# pectus.net
KiCad netlist of a schematic drawn in EAGLE
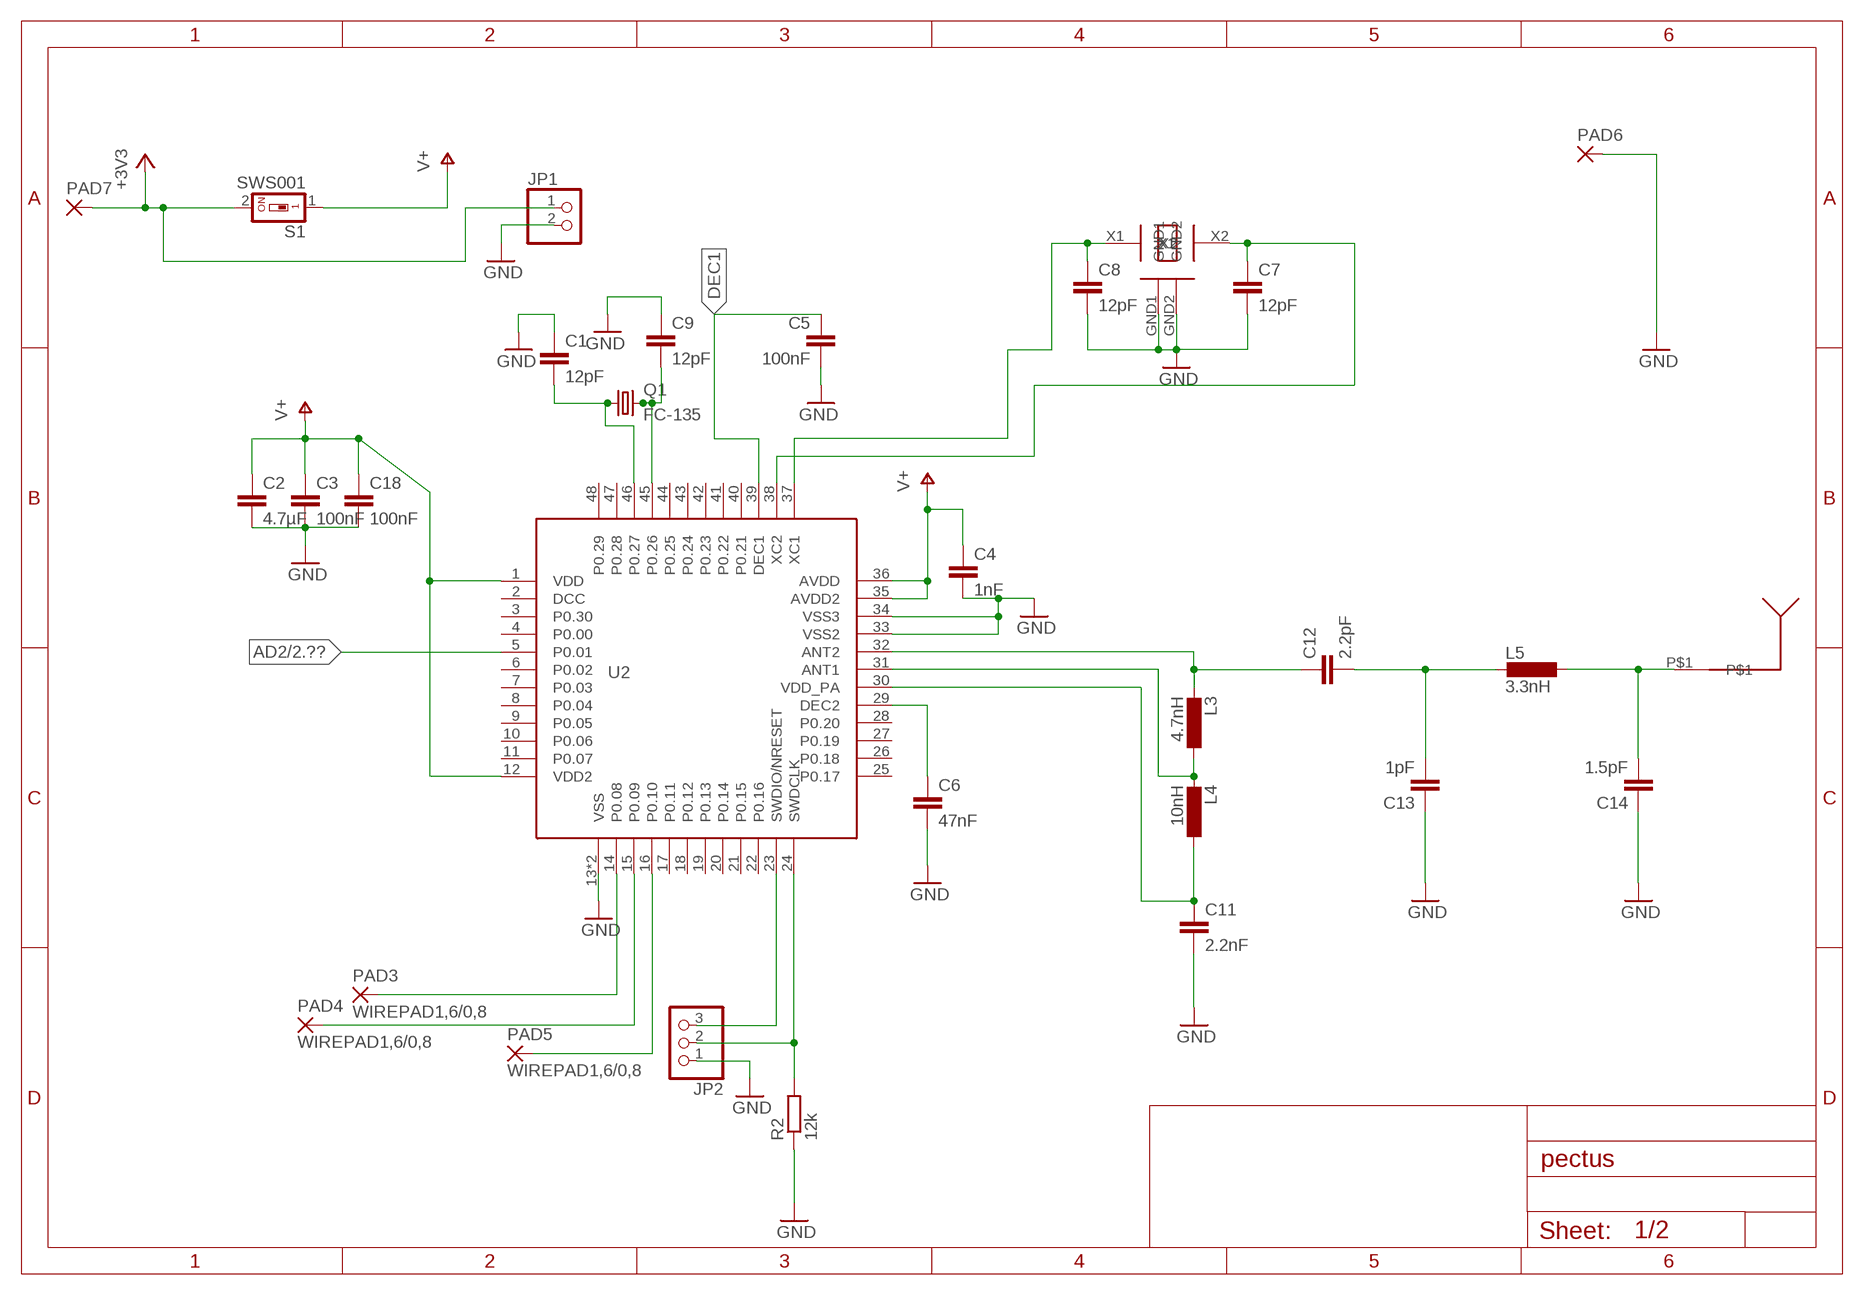
[diagram p0: schematic, sheet 1]
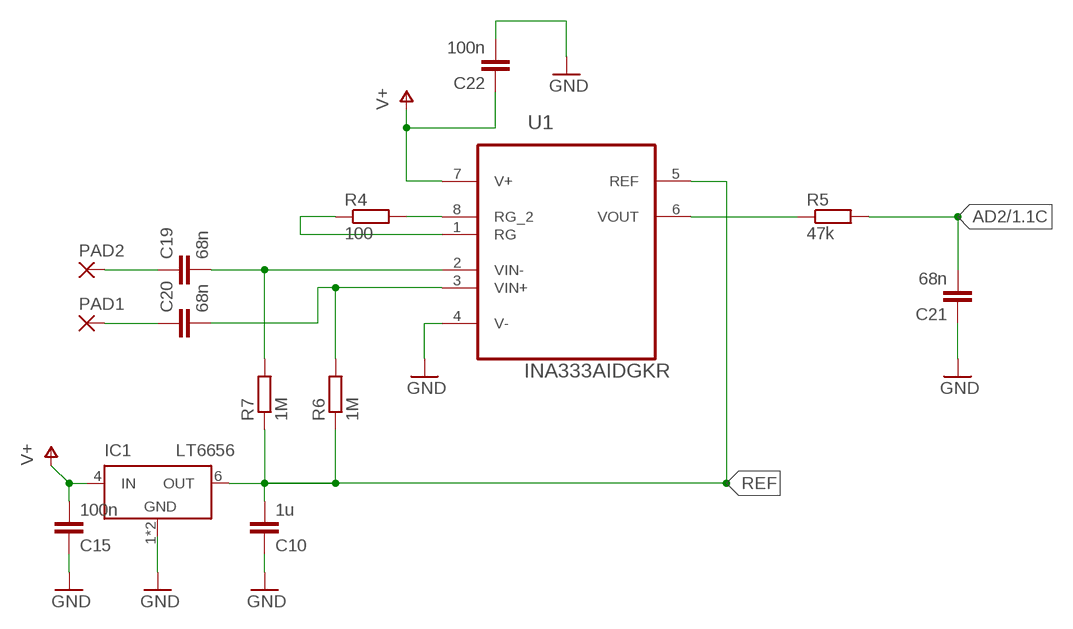
[diagram p1: schematic, sheet 2]

(export (version "E")
  (design (tool "Eeschema 10.0.6"))
  (components
    (comp (ref "C10")
      (value "1u")
      (footprint "eagle-import:C0603")
      (libsource (lib "eagle-import") (part "C-EUC0603"))
    )
    (comp (ref "C15")
      (value "100n")
      (footprint "eagle-import:C0603")
      (libsource (lib "eagle-import") (part "C-EUC0603"))
    )
    (comp (ref "C19")
      (value "68n")
      (footprint "eagle-import:C0603")
      (libsource (lib "eagle-import") (part "C-EUC0603"))
    )
    (comp (ref "C20")
      (value "68n")
      (footprint "eagle-import:C0603")
      (libsource (lib "eagle-import") (part "C-EUC0603"))
    )
    (comp (ref "C21")
      (value "68n")
      (footprint "eagle-import:C0603")
      (libsource (lib "eagle-import") (part "C-EUC0603"))
    )
    (comp (ref "C22")
      (value "100n")
      (footprint "eagle-import:C0603")
      (libsource (lib "eagle-import") (part "C-EUC0603"))
    )
    (comp (ref "IC1")
      (value "LT6656")
      (footprint "eagle-import:TSOT23-6")
      (libsource (lib "eagle-import") (part "LT6656"))
    )
    (comp (ref "PAD1")
      (value "1,6/0,8")
      (footprint "eagle-import:1,6_0,8")
      (libsource (lib "eagle-import") (part "1,6/0,8"))
    )
    (comp (ref "PAD2")
      (value "1,6/0,8")
      (footprint "eagle-import:1,6_0,8")
      (libsource (lib "eagle-import") (part "1,6/0,8"))
    )
    (comp (ref "R4")
      (value "100")
      (footprint "eagle-import:R0603")
      (libsource (lib "eagle-import") (part "R-EU_R0603"))
    )
    (comp (ref "R5")
      (value "47k")
      (footprint "eagle-import:R0603")
      (libsource (lib "eagle-import") (part "R-EU_R0603"))
    )
    (comp (ref "R6")
      (value "1M")
      (footprint "eagle-import:R0603")
      (libsource (lib "eagle-import") (part "R-EU_R0603"))
    )
    (comp (ref "R7")
      (value "1M")
      (footprint "eagle-import:R0603")
      (libsource (lib "eagle-import") (part "R-EU_R0603"))
    )
    (comp (ref "U1")
      (value "INA333AIDGKR")
      (footprint "eagle-import:SOP65P490X110-8N")
      (libsource (lib "eagle-import") (part "INA333AIDGKR"))
    )
    (comp (ref "C1")
      (value "12pF")
      (footprint "eagle-import:C0603K")
      (libsource (lib "eagle-import") (part "C-EUC0603K"))
    )
    (comp (ref "C2")
      (value "4.7µF")
      (footprint "eagle-import:C0603K")
      (libsource (lib "eagle-import") (part "C-EUC0603K"))
    )
    (comp (ref "C3")
      (value "100nF")
      (footprint "eagle-import:C0603K")
      (libsource (lib "eagle-import") (part "C-EUC0603K"))
    )
    (comp (ref "C4")
      (value "1nF")
      (footprint "eagle-import:C0603K")
      (libsource (lib "eagle-import") (part "C-EUC0603K"))
    )
    (comp (ref "C5")
      (value "100nF")
      (footprint "eagle-import:C0603K")
      (libsource (lib "eagle-import") (part "C-EUC0603K"))
    )
    (comp (ref "C6")
      (value "47nF")
      (footprint "eagle-import:C0603K")
      (libsource (lib "eagle-import") (part "C-EUC0603K"))
    )
    (comp (ref "C7")
      (value "12pF")
      (footprint "eagle-import:C0603K")
      (libsource (lib "eagle-import") (part "C-EUC0603K"))
    )
    (comp (ref "C8")
      (value "12pF")
      (footprint "eagle-import:C0603K")
      (libsource (lib "eagle-import") (part "C-EUC0603K"))
    )
    (comp (ref "C9")
      (value "12pF")
      (footprint "eagle-import:C0603K")
      (libsource (lib "eagle-import") (part "C-EUC0603K"))
    )
    (comp (ref "C11")
      (value "2.2nF")
      (footprint "eagle-import:C0603")
      (libsource (lib "eagle-import") (part "C-EUC0603"))
    )
    (comp (ref "C12")
      (value "2.2pF")
      (footprint "eagle-import:C0603")
      (libsource (lib "eagle-import") (part "C-EUC0603"))
    )
    (comp (ref "C13")
      (value "1pF")
      (footprint "eagle-import:C0603")
      (libsource (lib "eagle-import") (part "C-EUC0603"))
    )
    (comp (ref "C14")
      (value "1.5pF")
      (footprint "eagle-import:C0603")
      (libsource (lib "eagle-import") (part "C-EUC0603"))
    )
    (comp (ref "C18")
      (value "100nF")
      (footprint "eagle-import:C0603K")
      (libsource (lib "eagle-import") (part "C-EUC0603K"))
    )
    (comp (ref "JP1")
      (value "PINHD-1X2")
      (footprint "eagle-import:1X02")
      (libsource (lib "eagle-import") (part "PINHD-1X2"))
    )
    (comp (ref "JP2")
      (value "PINHD-1X3")
      (footprint "eagle-import:1X03")
      (libsource (lib "eagle-import") (part "PINHD-1X3"))
    )
    (comp (ref "L3")
      (value "4.7nH")
      (footprint "eagle-import:R0603")
      (libsource (lib "eagle-import") (part "L-EUL0603"))
    )
    (comp (ref "L4")
      (value "10nH")
      (footprint "eagle-import:R0603")
      (libsource (lib "eagle-import") (part "L-EUL0603"))
    )
    (comp (ref "L5")
      (value "3.3nH")
      (footprint "eagle-import:R0603")
      (libsource (lib "eagle-import") (part "L-EUL0603"))
    )
    (comp (ref "PAD3")
      (value "WIREPAD1,6/0,8")
      (footprint "eagle-import:1,6_0,8")
      (libsource (lib "eagle-import") (part "WIREPAD1,6/0,8"))
    )
    (comp (ref "PAD4")
      (value "WIREPAD1,6/0,8")
      (footprint "eagle-import:1,6_0,8")
      (libsource (lib "eagle-import") (part "WIREPAD1,6/0,8"))
    )
    (comp (ref "PAD5")
      (value "WIREPAD1,6/0,8")
      (footprint "eagle-import:1,6_0,8")
      (libsource (lib "eagle-import") (part "WIREPAD1,6/0,8"))
    )
    (comp (ref "PAD6")
      (value "SMD5")
      (footprint "eagle-import:SMD2,54-5,08")
      (libsource (lib "eagle-import") (part "SMD5"))
    )
    (comp (ref "PAD7")
      (value "SMD5")
      (footprint "eagle-import:SMD2,54-5,08")
      (libsource (lib "eagle-import") (part "SMD5"))
    )
    (comp (ref "Q1")
      (value "FC-135")
      (footprint "eagle-import:FC-135")
      (libsource (lib "eagle-import") (part "FC-135"))
    )
    (comp (ref "R2")
      (value "12k")
      (footprint "eagle-import:R0402")
      (libsource (lib "eagle-import") (part "R-EU_R0402"))
    )
    (comp (ref "S1")
      (value "SWS001")
      (footprint "eagle-import:SMS-001")
      (libsource (lib "eagle-import") (part "SWS001"))
    )
    (comp (ref "U$2")
      (value "AVX16MHZOSCILLATOR")
      (footprint "eagle-import:AVX16MHZOSCILLATOR")
      (libsource (lib "eagle-import") (part "AVX16MHZOSCILLATOR"))
    )
    (comp (ref "U$4")
      (value "ANTENNA")
      (footprint "eagle-import:ANTENNA")
      (libsource (lib "eagle-import") (part "ANTENNA"))
    )
    (comp (ref "U2")
      (value "NRF51822QFN")
      (footprint "eagle-import:QFN48(6X6)")
      (libsource (lib "eagle-import") (part "NRF51822QFN"))
    )
  )
  (nets
    (net (code "1") (name "+3V3") (class "Default")
      (node (ref "JP1") (pin "1") (pinfunction "1_1") (pintype "passive"))
      (node (ref "PAD7") (pin "1") (pinfunction "P_1") (pintype "passive"))
      (node (ref "S1") (pin "2") (pinfunction "2_2") (pintype "passive"))
    )
    (net (code "2") (name "AD2") (class "Default")
      (node (ref "C21") (pin "2") (pinfunction "2_2") (pintype "passive"))
      (node (ref "R5") (pin "2") (pinfunction "2_2") (pintype "passive"))
      (node (ref "U2") (pin "5") (pinfunction "P0.01_5") (pintype "bidirectional"))
    )
    (net (code "3") (name "DEC1") (class "Default")
      (node (ref "C5") (pin "1") (pinfunction "1_1") (pintype "passive"))
      (node (ref "U2") (pin "39") (pinfunction "DEC1_39") (pintype "bidirectional"))
    )
    (net (code "4") (name "GND") (class "Default")
      (node (ref "C1") (pin "1") (pinfunction "1_1") (pintype "passive"))
      (node (ref "C10") (pin "1") (pinfunction "1_1") (pintype "passive"))
      (node (ref "C11") (pin "2") (pinfunction "2_2") (pintype "passive"))
      (node (ref "C13") (pin "1") (pinfunction "1_1") (pintype "passive"))
      (node (ref "C14") (pin "1") (pinfunction "1_1") (pintype "passive"))
      (node (ref "C15") (pin "1") (pinfunction "1_1") (pintype "passive"))
      (node (ref "C18") (pin "2") (pinfunction "2_2") (pintype "passive"))
      (node (ref "C2") (pin "2") (pinfunction "2_2") (pintype "passive"))
      (node (ref "C21") (pin "1") (pinfunction "1_1") (pintype "passive"))
      (node (ref "C22") (pin "2") (pinfunction "2_2") (pintype "passive"))
      (node (ref "C3") (pin "2") (pinfunction "2_2") (pintype "passive"))
      (node (ref "C4") (pin "2") (pinfunction "2_2") (pintype "passive"))
      (node (ref "C5") (pin "2") (pinfunction "2_2") (pintype "passive"))
      (node (ref "C6") (pin "2") (pinfunction "2_2") (pintype "passive"))
      (node (ref "C7") (pin "2") (pinfunction "2_2") (pintype "passive"))
      (node (ref "C8") (pin "2") (pinfunction "2_2") (pintype "passive"))
      (node (ref "C9") (pin "1") (pinfunction "1_1") (pintype "passive"))
      (node (ref "IC1") (pin "1") (pinfunction "GND_1") (pintype "power_in"))
      (node (ref "IC1") (pin "2") (pinfunction "GND_2") (pintype "power_in"))
      (node (ref "JP1") (pin "2") (pinfunction "2_2") (pintype "passive"))
      (node (ref "JP2") (pin "1") (pinfunction "1_1") (pintype "passive"))
      (node (ref "PAD6") (pin "1") (pinfunction "P_1") (pintype "passive"))
      (node (ref "R2") (pin "1") (pinfunction "1_1") (pintype "passive"))
      (node (ref "U$2") (pin "GND1") (pinfunction "GND1_GND1") (pintype "bidirectional"))
      (node (ref "U$2") (pin "GND2") (pinfunction "GND2_GND2") (pintype "bidirectional"))
      (node (ref "U1") (pin "4") (pinfunction "V-_4") (pintype "power_in"))
      (node (ref "U2") (pin "13") (pinfunction "VSS_13") (pintype "bidirectional"))
      (node (ref "U2") (pin "33") (pinfunction "VSS2_33") (pintype "bidirectional"))
      (node (ref "U2") (pin "34") (pinfunction "VSS3_34") (pintype "bidirectional"))
      (node (ref "U2") (pin "P$49") (pinfunction "VSS_P$49") (pintype "bidirectional"))
    )
    (net (code "5") (name "Net-(C12-Pad2)") (class "Default")
      (node (ref "C12") (pin "2") (pinfunction "2_2") (pintype "passive"))
      (node (ref "C13") (pin "2") (pinfunction "2_2") (pintype "passive"))
      (node (ref "L5") (pin "2") (pinfunction "2_2") (pintype "passive"))
    )
    (net (code "6") (name "Net-(C14-Pad2)") (class "Default")
      (node (ref "C14") (pin "2") (pinfunction "2_2") (pintype "passive"))
      (node (ref "L5") (pin "1") (pinfunction "1_1") (pintype "passive"))
      (node (ref "U$4") (pin "P$1") (pinfunction "P$1_P$1") (pintype "bidirectional"))
    )
    (net (code "7") (name "Net-(PAD1-P)") (class "Default")
      (node (ref "C20") (pin "1") (pinfunction "1_1") (pintype "passive"))
      (node (ref "PAD1") (pin "1") (pinfunction "P_1") (pintype "passive"))
    )
    (net (code "8") (name "Net-(PAD2-P)") (class "Default")
      (node (ref "C19") (pin "1") (pinfunction "1_1") (pintype "passive"))
      (node (ref "PAD2") (pin "1") (pinfunction "P_1") (pintype "passive"))
    )
    (net (code "9") (name "Net-(PAD3-P)") (class "Default")
      (node (ref "PAD3") (pin "1") (pinfunction "P_1") (pintype "passive"))
      (node (ref "U2") (pin "14") (pinfunction "P0.08_14") (pintype "bidirectional"))
    )
    (net (code "10") (name "Net-(PAD4-P)") (class "Default")
      (node (ref "PAD4") (pin "1") (pinfunction "P_1") (pintype "passive"))
      (node (ref "U2") (pin "15") (pinfunction "P0.09_15") (pintype "bidirectional"))
    )
    (net (code "11") (name "Net-(PAD5-P)") (class "Default")
      (node (ref "PAD5") (pin "1") (pinfunction "P_1") (pintype "passive"))
      (node (ref "U2") (pin "16") (pinfunction "P0.10_16") (pintype "bidirectional"))
    )
    (net (code "12") (name "Net-(Q1-1)") (class "Default")
      (node (ref "C1") (pin "2") (pinfunction "2_2") (pintype "passive"))
      (node (ref "Q1") (pin "P$1") (pinfunction "1_P$1") (pintype "passive"))
      (node (ref "U2") (pin "46") (pinfunction "P0.27_46") (pintype "bidirectional"))
    )
    (net (code "13") (name "Net-(Q1-2)") (class "Default")
      (node (ref "C9") (pin "2") (pinfunction "2_2") (pintype "passive"))
      (node (ref "Q1") (pin "P$2") (pinfunction "2_P$2") (pintype "passive"))
      (node (ref "U2") (pin "45") (pinfunction "P0.26_45") (pintype "bidirectional"))
    )
    (net (code "14") (name "Net-(U1-RG)") (class "Default")
      (node (ref "R4") (pin "1") (pinfunction "1_1") (pintype "passive"))
      (node (ref "U1") (pin "1") (pinfunction "RG_1") (pintype "input"))
    )
    (net (code "15") (name "Net-(U1-RG_2)") (class "Default")
      (node (ref "R4") (pin "2") (pinfunction "2_2") (pintype "passive"))
      (node (ref "U1") (pin "8") (pinfunction "RG_2_8") (pintype "input"))
    )
    (net (code "16") (name "Net-(U1-VIN+)") (class "Default")
      (node (ref "C20") (pin "2") (pinfunction "2_2") (pintype "passive"))
      (node (ref "R6") (pin "2") (pinfunction "2_2") (pintype "passive"))
      (node (ref "U1") (pin "3") (pinfunction "VIN+_3") (pintype "input"))
    )
    (net (code "17") (name "Net-(U1-VIN-)") (class "Default")
      (node (ref "C19") (pin "2") (pinfunction "2_2") (pintype "passive"))
      (node (ref "R7") (pin "2") (pinfunction "2_2") (pintype "passive"))
      (node (ref "U1") (pin "2") (pinfunction "VIN-_2") (pintype "input"))
    )
    (net (code "18") (name "Net-(U1-VOUT)") (class "Default")
      (node (ref "R5") (pin "1") (pinfunction "1_1") (pintype "passive"))
      (node (ref "U1") (pin "6") (pinfunction "VOUT_6") (pintype "output"))
    )
    (net (code "19") (name "Net-(U2-ANT1)") (class "Default")
      (node (ref "L3") (pin "1") (pinfunction "1_1") (pintype "passive"))
      (node (ref "L4") (pin "2") (pinfunction "2_2") (pintype "passive"))
      (node (ref "U2") (pin "31") (pinfunction "ANT1_31") (pintype "bidirectional"))
    )
    (net (code "20") (name "Net-(U2-ANT2)") (class "Default")
      (node (ref "C12") (pin "1") (pinfunction "1_1") (pintype "passive"))
      (node (ref "L3") (pin "2") (pinfunction "2_2") (pintype "passive"))
      (node (ref "U2") (pin "32") (pinfunction "ANT2_32") (pintype "bidirectional"))
    )
    (net (code "21") (name "Net-(U2-DEC2)") (class "Default")
      (node (ref "C6") (pin "1") (pinfunction "1_1") (pintype "passive"))
      (node (ref "U2") (pin "29") (pinfunction "DEC2_29") (pintype "bidirectional"))
    )
    (net (code "22") (name "Net-(U2-SWDCLK)") (class "Default")
      (node (ref "JP2") (pin "2") (pinfunction "2_2") (pintype "passive"))
      (node (ref "R2") (pin "2") (pinfunction "2_2") (pintype "passive"))
      (node (ref "U2") (pin "24") (pinfunction "SWDCLK_24") (pintype "bidirectional"))
    )
    (net (code "23") (name "Net-(U2-SWDIO{slash}NRESET)") (class "Default")
      (node (ref "JP2") (pin "3") (pinfunction "3_3") (pintype "passive"))
      (node (ref "U2") (pin "23") (pinfunction "SWDIO/NRESET_23") (pintype "bidirectional"))
    )
    (net (code "24") (name "Net-(U2-VDD_PA)") (class "Default")
      (node (ref "C11") (pin "1") (pinfunction "1_1") (pintype "passive"))
      (node (ref "L4") (pin "1") (pinfunction "1_1") (pintype "passive"))
      (node (ref "U2") (pin "30") (pinfunction "VDD_PA_30") (pintype "bidirectional"))
    )
    (net (code "25") (name "Net-(U2-XC1)") (class "Default")
      (node (ref "C8") (pin "1") (pinfunction "1_1") (pintype "passive"))
      (node (ref "U$2") (pin "X1") (pinfunction "X1_X1") (pintype "bidirectional"))
      (node (ref "U2") (pin "37") (pinfunction "XC1_37") (pintype "bidirectional"))
    )
    (net (code "26") (name "Net-(U2-XC2)") (class "Default")
      (node (ref "C7") (pin "1") (pinfunction "1_1") (pintype "passive"))
      (node (ref "U$2") (pin "X2") (pinfunction "X2_X2") (pintype "bidirectional"))
      (node (ref "U2") (pin "38") (pinfunction "XC2_38") (pintype "bidirectional"))
    )
    (net (code "27") (name "REF") (class "Default")
      (node (ref "C10") (pin "2") (pinfunction "2_2") (pintype "passive"))
      (node (ref "IC1") (pin "6") (pinfunction "OUT_6") (pintype "output"))
      (node (ref "R6") (pin "1") (pinfunction "1_1") (pintype "passive"))
      (node (ref "R7") (pin "1") (pinfunction "1_1") (pintype "passive"))
      (node (ref "U1") (pin "5") (pinfunction "REF_5") (pintype "output"))
    )
    (net (code "28") (name "V+") (class "Default")
      (node (ref "C15") (pin "2") (pinfunction "2_2") (pintype "passive"))
      (node (ref "C18") (pin "1") (pinfunction "1_1") (pintype "passive"))
      (node (ref "C2") (pin "1") (pinfunction "1_1") (pintype "passive"))
      (node (ref "C22") (pin "1") (pinfunction "1_1") (pintype "passive"))
      (node (ref "C3") (pin "1") (pinfunction "1_1") (pintype "passive"))
      (node (ref "C4") (pin "1") (pinfunction "1_1") (pintype "passive"))
      (node (ref "IC1") (pin "4") (pinfunction "IN_4") (pintype "input"))
      (node (ref "S1") (pin "1") (pinfunction "1_1") (pintype "passive"))
      (node (ref "U1") (pin "7") (pinfunction "V+_7") (pintype "power_in"))
      (node (ref "U2") (pin "1") (pinfunction "VDD_1") (pintype "bidirectional"))
      (node (ref "U2") (pin "12") (pinfunction "VDD2_12") (pintype "bidirectional"))
      (node (ref "U2") (pin "35") (pinfunction "AVDD2_35") (pintype "bidirectional"))
      (node (ref "U2") (pin "36") (pinfunction "AVDD_36") (pintype "bidirectional"))
    )
    (net (code "29") (name "unconnected-(U2-DCC-Pad2)") (class "Default")
      (node (ref "U2") (pin "2") (pinfunction "DCC_2") (pintype "bidirectional"))
    )
    (net (code "30") (name "unconnected-(U2-P0.00-Pad4)") (class "Default")
      (node (ref "U2") (pin "4") (pinfunction "P0.00_4") (pintype "bidirectional"))
    )
    (net (code "31") (name "unconnected-(U2-P0.02-Pad6)") (class "Default")
      (node (ref "U2") (pin "6") (pinfunction "P0.02_6") (pintype "bidirectional"))
    )
    (net (code "32") (name "unconnected-(U2-P0.03-Pad7)") (class "Default")
      (node (ref "U2") (pin "7") (pinfunction "P0.03_7") (pintype "bidirectional"))
    )
    (net (code "33") (name "unconnected-(U2-P0.04-Pad8)") (class "Default")
      (node (ref "U2") (pin "8") (pinfunction "P0.04_8") (pintype "bidirectional"))
    )
    (net (code "34") (name "unconnected-(U2-P0.05-Pad9)") (class "Default")
      (node (ref "U2") (pin "9") (pinfunction "P0.05_9") (pintype "bidirectional"))
    )
    (net (code "35") (name "unconnected-(U2-P0.06-Pad10)") (class "Default")
      (node (ref "U2") (pin "10") (pinfunction "P0.06_10") (pintype "bidirectional"))
    )
    (net (code "36") (name "unconnected-(U2-P0.07-Pad11)") (class "Default")
      (node (ref "U2") (pin "11") (pinfunction "P0.07_11") (pintype "bidirectional"))
    )
    (net (code "37") (name "unconnected-(U2-P0.11-Pad17)") (class "Default")
      (node (ref "U2") (pin "17") (pinfunction "P0.11_17") (pintype "bidirectional"))
    )
    (net (code "38") (name "unconnected-(U2-P0.12-Pad18)") (class "Default")
      (node (ref "U2") (pin "18") (pinfunction "P0.12_18") (pintype "bidirectional"))
    )
    (net (code "39") (name "unconnected-(U2-P0.13-Pad19)") (class "Default")
      (node (ref "U2") (pin "19") (pinfunction "P0.13_19") (pintype "bidirectional"))
    )
    (net (code "40") (name "unconnected-(U2-P0.14-Pad20)") (class "Default")
      (node (ref "U2") (pin "20") (pinfunction "P0.14_20") (pintype "bidirectional"))
    )
    (net (code "41") (name "unconnected-(U2-P0.15-Pad21)") (class "Default")
      (node (ref "U2") (pin "21") (pinfunction "P0.15_21") (pintype "bidirectional"))
    )
    (net (code "42") (name "unconnected-(U2-P0.16-Pad22)") (class "Default")
      (node (ref "U2") (pin "22") (pinfunction "P0.16_22") (pintype "bidirectional"))
    )
    (net (code "43") (name "unconnected-(U2-P0.17-Pad25)") (class "Default")
      (node (ref "U2") (pin "25") (pinfunction "P0.17_25") (pintype "bidirectional"))
    )
    (net (code "44") (name "unconnected-(U2-P0.18-Pad26)") (class "Default")
      (node (ref "U2") (pin "26") (pinfunction "P0.18_26") (pintype "bidirectional"))
    )
    (net (code "45") (name "unconnected-(U2-P0.19-Pad27)") (class "Default")
      (node (ref "U2") (pin "27") (pinfunction "P0.19_27") (pintype "bidirectional"))
    )
    (net (code "46") (name "unconnected-(U2-P0.20-Pad28)") (class "Default")
      (node (ref "U2") (pin "28") (pinfunction "P0.20_28") (pintype "bidirectional"))
    )
    (net (code "47") (name "unconnected-(U2-P0.21-Pad40)") (class "Default")
      (node (ref "U2") (pin "40") (pinfunction "P0.21_40") (pintype "bidirectional"))
    )
    (net (code "48") (name "unconnected-(U2-P0.22-Pad41)") (class "Default")
      (node (ref "U2") (pin "41") (pinfunction "P0.22_41") (pintype "bidirectional"))
    )
    (net (code "49") (name "unconnected-(U2-P0.23-Pad42)") (class "Default")
      (node (ref "U2") (pin "42") (pinfunction "P0.23_42") (pintype "bidirectional"))
    )
    (net (code "50") (name "unconnected-(U2-P0.24-Pad43)") (class "Default")
      (node (ref "U2") (pin "43") (pinfunction "P0.24_43") (pintype "bidirectional"))
    )
    (net (code "51") (name "unconnected-(U2-P0.25-Pad44)") (class "Default")
      (node (ref "U2") (pin "44") (pinfunction "P0.25_44") (pintype "bidirectional"))
    )
    (net (code "52") (name "unconnected-(U2-P0.28-Pad47)") (class "Default")
      (node (ref "U2") (pin "47") (pinfunction "P0.28_47") (pintype "bidirectional"))
    )
    (net (code "53") (name "unconnected-(U2-P0.29-Pad48)") (class "Default")
      (node (ref "U2") (pin "48") (pinfunction "P0.29_48") (pintype "bidirectional"))
    )
    (net (code "54") (name "unconnected-(U2-P0.30-Pad3)") (class "Default")
      (node (ref "U2") (pin "3") (pinfunction "P0.30_3") (pintype "bidirectional"))
    )
  )
)
